# board.net
KiCad netlist of a schematic drawn in EAGLE
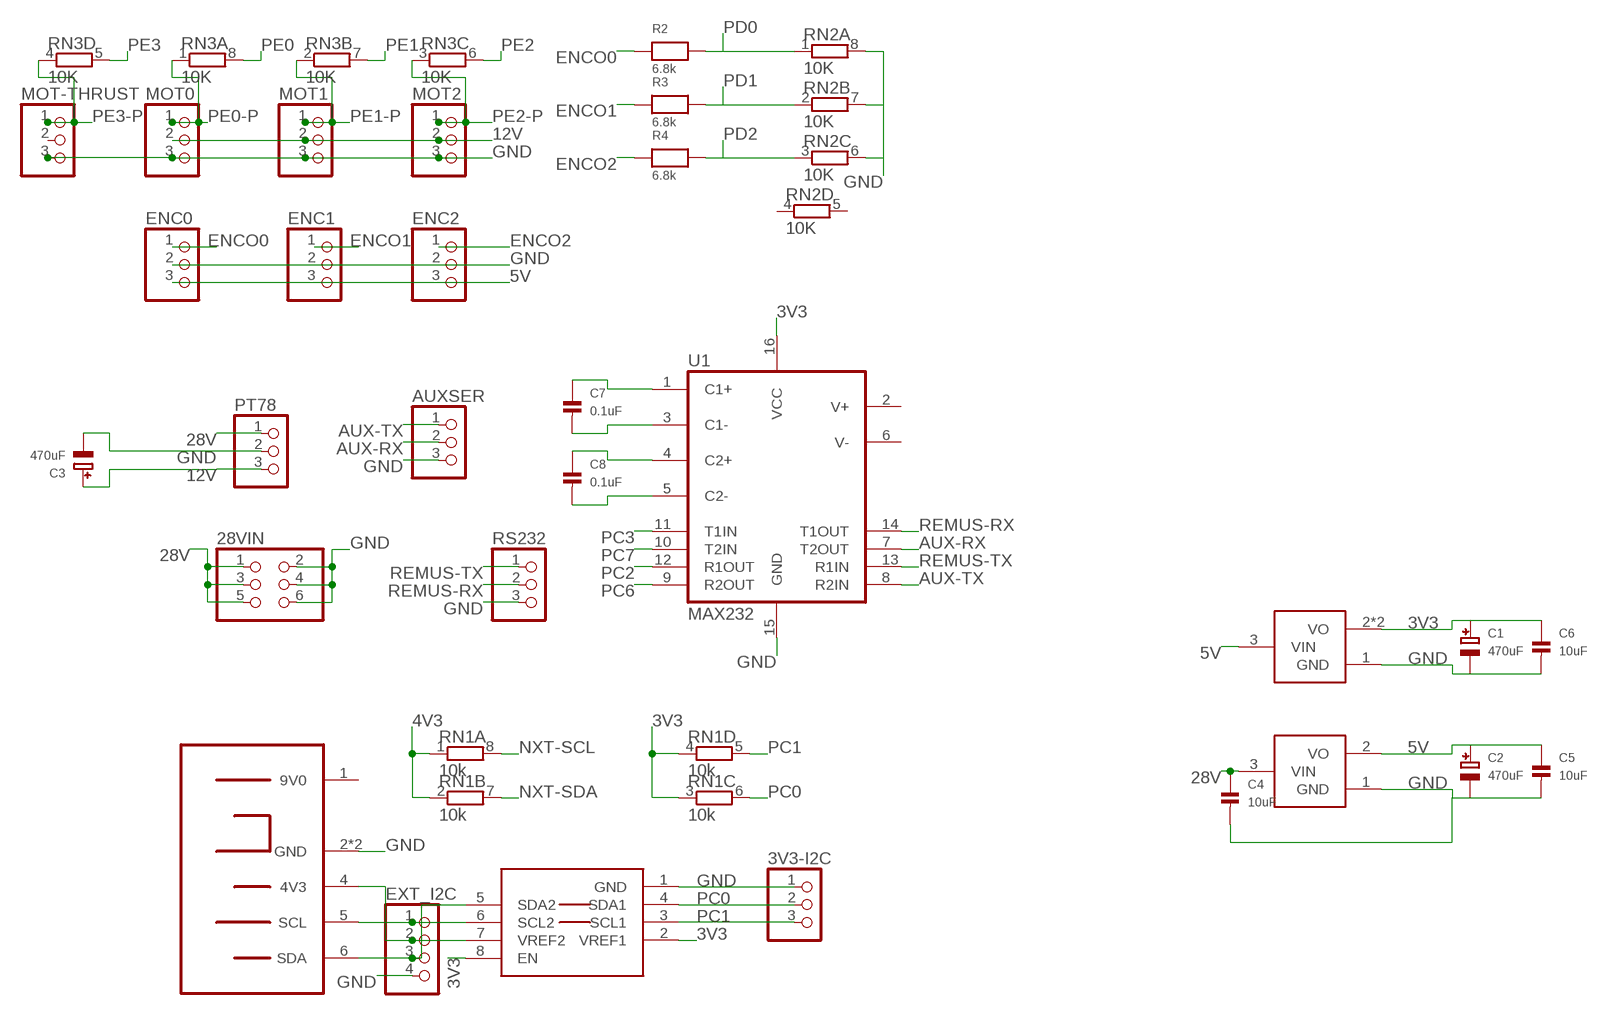
[diagram p0: schematic, sheet 1]
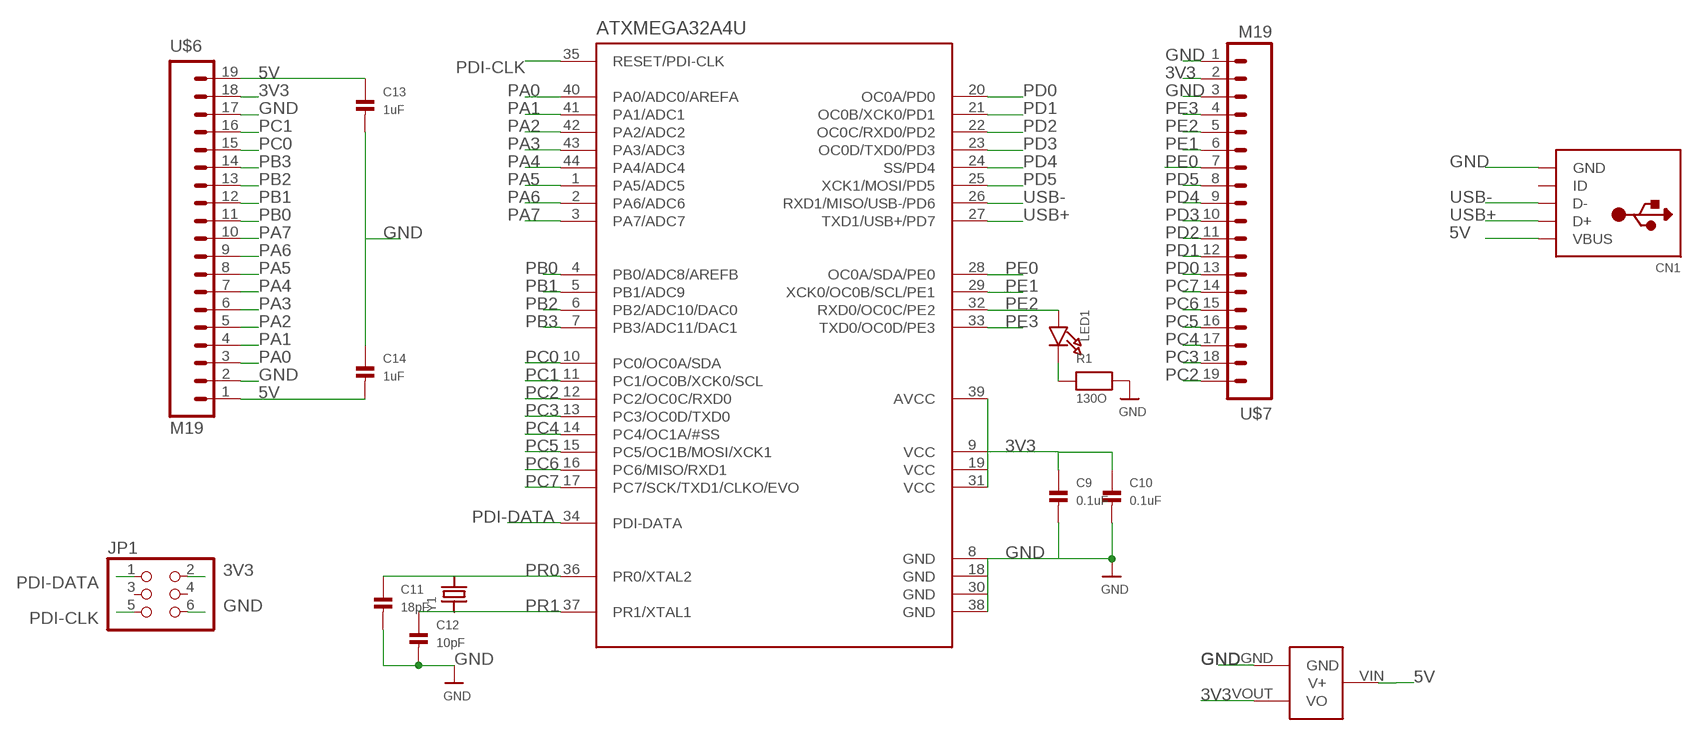
[diagram p1: schematic, sheet 2]

(export (version "E")
  (design (tool "Eeschema 10.0.6"))
  (components
    (comp (ref "ATXMEGA32A4U")
      (value "ATXMEGAXXA4U-AU")
      (footprint "eagle-import:TQFP-44")
      (libsource (lib "eagle-import") (part "ATXMEGAXXA4U-AU"))
    )
    (comp (ref "C9")
      (value "0.1uF")
      (footprint "eagle-import:0603")
      (libsource (lib "eagle-import") (part "CAP_CERAMIC0603"))
    )
    (comp (ref "C10")
      (value "0.1uF")
      (footprint "eagle-import:0603")
      (libsource (lib "eagle-import") (part "CAP_CERAMIC0603"))
    )
    (comp (ref "C11")
      (value "18pF")
      (footprint "eagle-import:0603")
      (libsource (lib "eagle-import") (part "CAP_CERAMIC0603"))
    )
    (comp (ref "C12")
      (value "10pF")
      (footprint "eagle-import:0603")
      (libsource (lib "eagle-import") (part "CAP_CERAMIC0603"))
    )
    (comp (ref "C13")
      (value "1uF")
      (footprint "eagle-import:0603")
      (libsource (lib "eagle-import") (part "CAP_CERAMIC0603"))
    )
    (comp (ref "C14")
      (value "1uF")
      (footprint "eagle-import:0603")
      (libsource (lib "eagle-import") (part "CAP_CERAMIC0603"))
    )
    (comp (ref "CN1")
      (value "USBMICROB")
      (footprint "eagle-import:USB-MICROB")
      (libsource (lib "eagle-import") (part "USBMICROB"))
    )
    (comp (ref "JP1")
      (value "HEADER-2X3")
      (footprint "eagle-import:2X03")
      (libsource (lib "eagle-import") (part "HEADER-2X3"))
    )
    (comp (ref "LED1")
      (value "LED0603")
      (footprint "eagle-import:CHIPLED_0603")
      (libsource (lib "eagle-import") (part "LED0603"))
    )
    (comp (ref "R1")
      (value "130O")
      (footprint "eagle-import:0603")
      (libsource (lib "eagle-import") (part "RESISTOR0603"))
    )
    (comp (ref "U$5")
      (value "MCP1700")
      (footprint "eagle-import:SOT23-3")
      (libsource (lib "eagle-import") (part "MCP1700"))
    )
    (comp (ref "U$6")
      (value "M19")
      (footprint "eagle-import:1X19")
      (libsource (lib "eagle-import") (part "M19"))
    )
    (comp (ref "U$7")
      (value "M19")
      (footprint "eagle-import:1X19")
      (libsource (lib "eagle-import") (part "M19"))
    )
    (comp (ref "Y1")
      (value "CRYSTAL")
      (footprint "eagle-import:NX8045GB")
      (libsource (lib "eagle-import") (part "CRYSTAL"))
    )
    (comp (ref "3V3-I2C")
      (value "HEADER-1X3ROUND")
      (footprint "eagle-import:1X03_ROUND")
      (libsource (lib "eagle-import") (part "HEADER-1X3ROUND"))
    )
    (comp (ref "28VIN")
      (value "HEADER-2X3")
      (footprint "eagle-import:2X03")
      (libsource (lib "eagle-import") (part "HEADER-2X3"))
    )
    (comp (ref "AUXSER")
      (value "HEADER-1X3ROUND")
      (footprint "eagle-import:1X03_ROUND")
      (libsource (lib "eagle-import") (part "HEADER-1X3ROUND"))
    )
    (comp (ref "C1")
      (value "470uF")
      (footprint "eagle-import:EIA7343-31_D-W")
      (libsource (lib "eagle-import") (part "CAP_TANTALUMD/7343_WAVE"))
    )
    (comp (ref "C2")
      (value "470uF")
      (footprint "eagle-import:EIA7343-31_D-W")
      (libsource (lib "eagle-import") (part "CAP_TANTALUMD/7343_WAVE"))
    )
    (comp (ref "C3")
      (value "470uF")
      (footprint "eagle-import:EIA7343-31_D-W")
      (libsource (lib "eagle-import") (part "CAP_TANTALUMD/7343_WAVE"))
    )
    (comp (ref "C4")
      (value "10uF")
      (footprint "eagle-import:1206")
      (libsource (lib "eagle-import") (part "CAP_CERAMIC1206"))
    )
    (comp (ref "C5")
      (value "10uF")
      (footprint "eagle-import:1206")
      (libsource (lib "eagle-import") (part "CAP_CERAMIC1206"))
    )
    (comp (ref "C6")
      (value "10uF")
      (footprint "eagle-import:1206")
      (libsource (lib "eagle-import") (part "CAP_CERAMIC1206"))
    )
    (comp (ref "C7")
      (value "0.1uF")
      (footprint "eagle-import:0603")
      (libsource (lib "eagle-import") (part "CAP_CERAMIC0603"))
    )
    (comp (ref "C8")
      (value "0.1uF")
      (footprint "eagle-import:0603")
      (libsource (lib "eagle-import") (part "CAP_CERAMIC0603"))
    )
    (comp (ref "ENC0")
      (value "HEADER-1X3ROUND")
      (footprint "eagle-import:1X03_ROUND")
      (libsource (lib "eagle-import") (part "HEADER-1X3ROUND"))
    )
    (comp (ref "ENC1")
      (value "HEADER-1X3ROUND")
      (footprint "eagle-import:1X03_ROUND")
      (libsource (lib "eagle-import") (part "HEADER-1X3ROUND"))
    )
    (comp (ref "ENC2")
      (value "HEADER-1X3ROUND")
      (footprint "eagle-import:1X03_ROUND")
      (libsource (lib "eagle-import") (part "HEADER-1X3ROUND"))
    )
    (comp (ref "EXT_I2C")
      (value "HEADER-1X4ROUND")
      (footprint "eagle-import:1X04_ROUND")
      (libsource (lib "eagle-import") (part "HEADER-1X4ROUND"))
    )
    (comp (ref "MOT-THRUST")
      (value "HEADER-1X3ROUND")
      (footprint "eagle-import:1X03_ROUND")
      (libsource (lib "eagle-import") (part "HEADER-1X3ROUND"))
    )
    (comp (ref "MOT0")
      (value "HEADER-1X3ROUND")
      (footprint "eagle-import:1X03_ROUND")
      (libsource (lib "eagle-import") (part "HEADER-1X3ROUND"))
    )
    (comp (ref "MOT1")
      (value "HEADER-1X3ROUND")
      (footprint "eagle-import:1X03_ROUND")
      (libsource (lib "eagle-import") (part "HEADER-1X3ROUND"))
    )
    (comp (ref "MOT2")
      (value "HEADER-1X3ROUND")
      (footprint "eagle-import:1X03_ROUND")
      (libsource (lib "eagle-import") (part "HEADER-1X3ROUND"))
    )
    (comp (ref "PT78")
      (value "HEADER-1X3ROUND")
      (footprint "eagle-import:1X03_ROUND")
      (libsource (lib "eagle-import") (part "HEADER-1X3ROUND"))
    )
    (comp (ref "R2")
      (value "6.8k")
      (footprint "eagle-import:0603")
      (libsource (lib "eagle-import") (part "RESISTOR0603"))
    )
    (comp (ref "R3")
      (value "6.8k")
      (footprint "eagle-import:0603")
      (libsource (lib "eagle-import") (part "RESISTOR0603"))
    )
    (comp (ref "R4")
      (value "6.8k")
      (footprint "eagle-import:0603")
      (libsource (lib "eagle-import") (part "RESISTOR0603"))
    )
    (comp (ref "RN1")
      (value "10k")
      (footprint "eagle-import:RN8P-4R-CRA06S")
      (libsource (lib "eagle-import") (part "RNETWORK"))
    )
    (comp (ref "RN2")
      (value "10K")
      (footprint "eagle-import:RN8P-4R-CRA06S")
      (libsource (lib "eagle-import") (part "RNETWORK"))
    )
    (comp (ref "RN3")
      (value "10K")
      (footprint "eagle-import:RN8P-4R-CRA06S")
      (libsource (lib "eagle-import") (part "RNETWORK"))
    )
    (comp (ref "RS232")
      (value "HEADER-1X3ROUND")
      (footprint "eagle-import:1X03_ROUND")
      (libsource (lib "eagle-import") (part "HEADER-1X3ROUND"))
    )
    (comp (ref "U$1")
      (value "PCA9306")
      (footprint "eagle-import:SO-08")
      (libsource (lib "eagle-import") (part "PCA9306"))
    )
    (comp (ref "U$2")
      (value "NXT-CONNECTOR")
      (footprint "eagle-import:NXT-FOOTPRINT")
      (libsource (lib "eagle-import") (part "NXT-CONNECTOR"))
    )
    (comp (ref "U$3")
      (value "VREGAP1117")
      (footprint "eagle-import:SOT223")
      (libsource (lib "eagle-import") (part "VREGAP1117"))
    )
    (comp (ref "U$4")
      (value "VREGIFX27001")
      (footprint "eagle-import:TO252")
      (libsource (lib "eagle-import") (part "VREGIFX27001"))
    )
    (comp (ref "U1")
      (value "MAX232")
      (footprint "eagle-import:SO-16")
      (libsource (lib "eagle-import") (part "MAX232"))
    )
  )
  (nets
    (net (code "1") (name "3V3") (class "Default")
      (node (ref "ATXMEGA32A4U") (pin "19") (pinfunction "VCC_19") (pintype "power_in"))
      (node (ref "ATXMEGA32A4U") (pin "31") (pinfunction "VCC_31") (pintype "power_in"))
      (node (ref "ATXMEGA32A4U") (pin "39") (pinfunction "AVCC_39") (pintype "power_in"))
      (node (ref "ATXMEGA32A4U") (pin "9") (pinfunction "VCC_9") (pintype "power_in"))
      (node (ref "C1") (pin "+") (pinfunction "+_+") (pintype "passive"))
      (node (ref "C10") (pin "1") (pinfunction "P$1_1") (pintype "passive"))
      (node (ref "C6") (pin "1") (pinfunction "P$1_1") (pintype "passive"))
      (node (ref "C9") (pin "1") (pinfunction "P$1_1") (pintype "passive"))
      (node (ref "JP1") (pin "2") (pinfunction "2_2") (pintype "passive"))
      (node (ref "RN1") (pin "3") (pinfunction "1_3") (pintype "passive"))
      (node (ref "RN1") (pin "4") (pinfunction "1_4") (pintype "passive"))
      (node (ref "U$1") (pin "2") (pinfunction "VREF1_2") (pintype "bidirectional"))
      (node (ref "U$1") (pin "8") (pinfunction "EN_8") (pintype "bidirectional"))
      (node (ref "U$3") (pin "2") (pinfunction "VO_2") (pintype "bidirectional"))
      (node (ref "U$3") (pin "4") (pinfunction "VO_4") (pintype "bidirectional"))
      (node (ref "U$5") (pin "VOUT") (pinfunction "VO_VOUT") (pintype "bidirectional"))
      (node (ref "U$6") (pin "18") (pinfunction "18_18") (pintype "passive"))
      (node (ref "U$7") (pin "2") (pinfunction "2_2") (pintype "passive"))
      (node (ref "U1") (pin "16") (pinfunction "VCC_16") (pintype "bidirectional"))
    )
    (net (code "2") (name "4V3") (class "Default")
      (node (ref "EXT_I2C") (pin "2") (pinfunction "2_2") (pintype "passive"))
      (node (ref "RN1") (pin "1") (pinfunction "1_1") (pintype "passive"))
      (node (ref "RN1") (pin "2") (pinfunction "1_2") (pintype "passive"))
      (node (ref "U$1") (pin "7") (pinfunction "VREF2_7") (pintype "bidirectional"))
      (node (ref "U$2") (pin "4") (pinfunction "4V3_4") (pintype "bidirectional"))
    )
    (net (code "3") (name "5V") (class "Default")
      (node (ref "C13") (pin "1") (pinfunction "P$1_1") (pintype "passive"))
      (node (ref "C14") (pin "2") (pinfunction "P$2_2") (pintype "passive"))
      (node (ref "C2") (pin "+") (pinfunction "+_+") (pintype "passive"))
      (node (ref "C5") (pin "1") (pinfunction "P$1_1") (pintype "passive"))
      (node (ref "CN1") (pin "P1") (pinfunction "VBUS_P1") (pintype "power_in"))
      (node (ref "ENC0") (pin "3") (pinfunction "3_3") (pintype "passive"))
      (node (ref "ENC1") (pin "3") (pinfunction "3_3") (pintype "passive"))
      (node (ref "ENC2") (pin "3") (pinfunction "3_3") (pintype "passive"))
      (node (ref "U$3") (pin "3") (pinfunction "VIN_3") (pintype "bidirectional"))
      (node (ref "U$4") (pin "2") (pinfunction "VO_2") (pintype "bidirectional"))
      (node (ref "U$5") (pin "VIN") (pinfunction "V+_VIN") (pintype "bidirectional"))
      (node (ref "U$6") (pin "1") (pinfunction "1_1") (pintype "passive"))
      (node (ref "U$6") (pin "19") (pinfunction "19_19") (pintype "passive"))
    )
    (net (code "4") (name "12V") (class "Default")
      (node (ref "C3") (pin "+") (pinfunction "+_+") (pintype "passive"))
      (node (ref "MOT0") (pin "2") (pinfunction "2_2") (pintype "passive"))
      (node (ref "MOT1") (pin "2") (pinfunction "2_2") (pintype "passive"))
      (node (ref "MOT2") (pin "2") (pinfunction "2_2") (pintype "passive"))
      (node (ref "PT78") (pin "3") (pinfunction "3_3") (pintype "passive"))
    )
    (net (code "5") (name "28V") (class "Default")
      (node (ref "28VIN") (pin "1") (pinfunction "1_1") (pintype "passive"))
      (node (ref "28VIN") (pin "3") (pinfunction "3_3") (pintype "passive"))
      (node (ref "28VIN") (pin "5") (pinfunction "5_5") (pintype "passive"))
      (node (ref "C4") (pin "1") (pinfunction "P$1_1") (pintype "passive"))
      (node (ref "PT78") (pin "1") (pinfunction "1_1") (pintype "passive"))
      (node (ref "U$4") (pin "3") (pinfunction "VIN_3") (pintype "bidirectional"))
    )
    (net (code "6") (name "AUX-RX") (class "Default")
      (node (ref "AUXSER") (pin "2") (pinfunction "2_2") (pintype "passive"))
      (node (ref "U1") (pin "7") (pinfunction "T2OUT_7") (pintype "output"))
    )
    (net (code "7") (name "AUX-TX") (class "Default")
      (node (ref "AUXSER") (pin "1") (pinfunction "1_1") (pintype "passive"))
      (node (ref "U1") (pin "8") (pinfunction "R2IN_8") (pintype "input"))
    )
    (net (code "8") (name "ENCO0") (class "Default")
      (node (ref "ENC0") (pin "1") (pinfunction "1_1") (pintype "passive"))
      (node (ref "R2") (pin "1") (pinfunction "1_1") (pintype "passive"))
    )
    (net (code "9") (name "ENCO1") (class "Default")
      (node (ref "ENC1") (pin "1") (pinfunction "1_1") (pintype "passive"))
      (node (ref "R3") (pin "1") (pinfunction "1_1") (pintype "passive"))
    )
    (net (code "10") (name "ENCO2") (class "Default")
      (node (ref "ENC2") (pin "1") (pinfunction "1_1") (pintype "passive"))
      (node (ref "R4") (pin "1") (pinfunction "1_1") (pintype "passive"))
    )
    (net (code "11") (name "GND") (class "Default")
      (node (ref "28VIN") (pin "2") (pinfunction "2_2") (pintype "passive"))
      (node (ref "28VIN") (pin "4") (pinfunction "4_4") (pintype "passive"))
      (node (ref "28VIN") (pin "6") (pinfunction "6_6") (pintype "passive"))
      (node (ref "3V3-I2C") (pin "1") (pinfunction "1_1") (pintype "passive"))
      (node (ref "ATXMEGA32A4U") (pin "18") (pinfunction "GND_18") (pintype "power_in"))
      (node (ref "ATXMEGA32A4U") (pin "30") (pinfunction "GND_30") (pintype "power_in"))
      (node (ref "ATXMEGA32A4U") (pin "38") (pinfunction "GND_38") (pintype "power_in"))
      (node (ref "ATXMEGA32A4U") (pin "8") (pinfunction "GND_8") (pintype "power_in"))
      (node (ref "AUXSER") (pin "3") (pinfunction "3_3") (pintype "passive"))
      (node (ref "C1") (pin "-") (pinfunction "-_-") (pintype "passive"))
      (node (ref "C10") (pin "2") (pinfunction "P$2_2") (pintype "passive"))
      (node (ref "C11") (pin "2") (pinfunction "P$2_2") (pintype "passive"))
      (node (ref "C12") (pin "2") (pinfunction "P$2_2") (pintype "passive"))
      (node (ref "C13") (pin "2") (pinfunction "P$2_2") (pintype "passive"))
      (node (ref "C14") (pin "1") (pinfunction "P$1_1") (pintype "passive"))
      (node (ref "C3") (pin "-") (pinfunction "-_-") (pintype "passive"))
      (node (ref "C4") (pin "2") (pinfunction "P$2_2") (pintype "passive"))
      (node (ref "C5") (pin "2") (pinfunction "P$2_2") (pintype "passive"))
      (node (ref "C6") (pin "2") (pinfunction "P$2_2") (pintype "passive"))
      (node (ref "C9") (pin "2") (pinfunction "P$2_2") (pintype "passive"))
      (node (ref "CN1") (pin "P5") (pinfunction "GND_P5") (pintype "power_in"))
      (node (ref "ENC0") (pin "2") (pinfunction "2_2") (pintype "passive"))
      (node (ref "ENC1") (pin "2") (pinfunction "2_2") (pintype "passive"))
      (node (ref "ENC2") (pin "2") (pinfunction "2_2") (pintype "passive"))
      (node (ref "EXT_I2C") (pin "4") (pinfunction "4_4") (pintype "passive"))
      (node (ref "JP1") (pin "6") (pinfunction "6_6") (pintype "passive"))
      (node (ref "MOT-THRUST") (pin "3") (pinfunction "3_3") (pintype "passive"))
      (node (ref "MOT0") (pin "3") (pinfunction "3_3") (pintype "passive"))
      (node (ref "MOT1") (pin "3") (pinfunction "3_3") (pintype "passive"))
      (node (ref "MOT2") (pin "3") (pinfunction "3_3") (pintype "passive"))
      (node (ref "PT78") (pin "2") (pinfunction "2_2") (pintype "passive"))
      (node (ref "R1") (pin "2") (pinfunction "2_2") (pintype "passive"))
      (node (ref "RN2") (pin "6") (pinfunction "2_6") (pintype "passive"))
      (node (ref "RN2") (pin "7") (pinfunction "2_7") (pintype "passive"))
      (node (ref "RN2") (pin "8") (pinfunction "2_8") (pintype "passive"))
      (node (ref "RS232") (pin "3") (pinfunction "3_3") (pintype "passive"))
      (node (ref "U$1") (pin "1") (pinfunction "GND_1") (pintype "bidirectional"))
      (node (ref "U$2") (pin "2") (pinfunction "GND_2") (pintype "bidirectional"))
      (node (ref "U$2") (pin "3") (pinfunction "GND_3") (pintype "bidirectional"))
      (node (ref "U$3") (pin "1") (pinfunction "GND_1") (pintype "bidirectional"))
      (node (ref "U$4") (pin "1") (pinfunction "GND_1") (pintype "bidirectional"))
      (node (ref "U$5") (pin "GND") (pinfunction "GND_GND") (pintype "bidirectional"))
      (node (ref "U$6") (pin "17") (pinfunction "17_17") (pintype "passive"))
      (node (ref "U$6") (pin "2") (pinfunction "2_2") (pintype "passive"))
      (node (ref "U$7") (pin "1") (pinfunction "1_1") (pintype "passive"))
      (node (ref "U$7") (pin "3") (pinfunction "3_3") (pintype "passive"))
      (node (ref "U1") (pin "15") (pinfunction "GND_15") (pintype "bidirectional"))
    )
    (net (code "12") (name "NXT-SCL") (class "Default")
      (node (ref "EXT_I2C") (pin "1") (pinfunction "1_1") (pintype "passive"))
      (node (ref "RN1") (pin "8") (pinfunction "2_8") (pintype "passive"))
      (node (ref "U$1") (pin "6") (pinfunction "SCL2_6") (pintype "bidirectional"))
      (node (ref "U$2") (pin "5") (pinfunction "SCL_5") (pintype "bidirectional"))
    )
    (net (code "13") (name "NXT-SDA") (class "Default")
      (node (ref "EXT_I2C") (pin "3") (pinfunction "3_3") (pintype "passive"))
      (node (ref "RN1") (pin "7") (pinfunction "2_7") (pintype "passive"))
      (node (ref "U$1") (pin "5") (pinfunction "SDA2_5") (pintype "bidirectional"))
      (node (ref "U$2") (pin "6") (pinfunction "SDA_6") (pintype "bidirectional"))
    )
    (net (code "14") (name "Net-(C7-P$1)") (class "Default")
      (node (ref "C7") (pin "1") (pinfunction "P$1_1") (pintype "passive"))
      (node (ref "U1") (pin "1") (pinfunction "C1+_1") (pintype "bidirectional"))
    )
    (net (code "15") (name "Net-(C7-P$2)") (class "Default")
      (node (ref "C7") (pin "2") (pinfunction "P$2_2") (pintype "passive"))
      (node (ref "U1") (pin "3") (pinfunction "C1-_3") (pintype "bidirectional"))
    )
    (net (code "16") (name "Net-(C8-P$1)") (class "Default")
      (node (ref "C8") (pin "1") (pinfunction "P$1_1") (pintype "passive"))
      (node (ref "U1") (pin "4") (pinfunction "C2+_4") (pintype "bidirectional"))
    )
    (net (code "17") (name "Net-(C8-P$2)") (class "Default")
      (node (ref "C8") (pin "2") (pinfunction "P$2_2") (pintype "passive"))
      (node (ref "U1") (pin "5") (pinfunction "C2-_5") (pintype "bidirectional"))
    )
    (net (code "18") (name "Net-(LED1-PadC)") (class "Default")
      (node (ref "LED1") (pin "C") (pinfunction "C_C") (pintype "passive"))
      (node (ref "R1") (pin "1") (pinfunction "1_1") (pintype "passive"))
    )
    (net (code "19") (name "PA0") (class "Default")
      (node (ref "ATXMEGA32A4U") (pin "40") (pinfunction "PA0/ADC0/AREFA_40") (pintype "bidirectional"))
      (node (ref "U$6") (pin "3") (pinfunction "3_3") (pintype "passive"))
    )
    (net (code "20") (name "PA1") (class "Default")
      (node (ref "ATXMEGA32A4U") (pin "41") (pinfunction "PA1/ADC1_41") (pintype "bidirectional"))
      (node (ref "U$6") (pin "4") (pinfunction "4_4") (pintype "passive"))
    )
    (net (code "21") (name "PA2") (class "Default")
      (node (ref "ATXMEGA32A4U") (pin "42") (pinfunction "PA2/ADC2_42") (pintype "bidirectional"))
      (node (ref "U$6") (pin "5") (pinfunction "5_5") (pintype "passive"))
    )
    (net (code "22") (name "PA3") (class "Default")
      (node (ref "ATXMEGA32A4U") (pin "43") (pinfunction "PA3/ADC3_43") (pintype "bidirectional"))
      (node (ref "U$6") (pin "6") (pinfunction "6_6") (pintype "passive"))
    )
    (net (code "23") (name "PA4") (class "Default")
      (node (ref "ATXMEGA32A4U") (pin "44") (pinfunction "PA4/ADC4_44") (pintype "bidirectional"))
      (node (ref "U$6") (pin "7") (pinfunction "7_7") (pintype "passive"))
    )
    (net (code "24") (name "PA5") (class "Default")
      (node (ref "ATXMEGA32A4U") (pin "1") (pinfunction "PA5/ADC5_1") (pintype "bidirectional"))
      (node (ref "U$6") (pin "8") (pinfunction "8_8") (pintype "passive"))
    )
    (net (code "25") (name "PA6") (class "Default")
      (node (ref "ATXMEGA32A4U") (pin "2") (pinfunction "PA6/ADC6_2") (pintype "bidirectional"))
      (node (ref "U$6") (pin "9") (pinfunction "9_9") (pintype "passive"))
    )
    (net (code "26") (name "PA7") (class "Default")
      (node (ref "ATXMEGA32A4U") (pin "3") (pinfunction "PA7/ADC7_3") (pintype "bidirectional"))
      (node (ref "U$6") (pin "10") (pinfunction "10_10") (pintype "passive"))
    )
    (net (code "27") (name "PB0") (class "Default")
      (node (ref "ATXMEGA32A4U") (pin "4") (pinfunction "PB0/ADC8/AREFB_4") (pintype "bidirectional"))
      (node (ref "U$6") (pin "11") (pinfunction "11_11") (pintype "passive"))
    )
    (net (code "28") (name "PB1") (class "Default")
      (node (ref "ATXMEGA32A4U") (pin "5") (pinfunction "PB1/ADC9_5") (pintype "bidirectional"))
      (node (ref "U$6") (pin "12") (pinfunction "12_12") (pintype "passive"))
    )
    (net (code "29") (name "PB2") (class "Default")
      (node (ref "ATXMEGA32A4U") (pin "6") (pinfunction "PB2/ADC10/DAC0_6") (pintype "bidirectional"))
      (node (ref "U$6") (pin "13") (pinfunction "13_13") (pintype "passive"))
    )
    (net (code "30") (name "PB3") (class "Default")
      (node (ref "ATXMEGA32A4U") (pin "7") (pinfunction "PB3/ADC11/DAC1_7") (pintype "bidirectional"))
      (node (ref "U$6") (pin "14") (pinfunction "14_14") (pintype "passive"))
    )
    (net (code "31") (name "PC0") (class "Default")
      (node (ref "3V3-I2C") (pin "2") (pinfunction "2_2") (pintype "passive"))
      (node (ref "ATXMEGA32A4U") (pin "10") (pinfunction "PC0/OC0A/SDA_10") (pintype "bidirectional"))
      (node (ref "RN1") (pin "6") (pinfunction "2_6") (pintype "passive"))
      (node (ref "U$1") (pin "4") (pinfunction "SDA1_4") (pintype "bidirectional"))
      (node (ref "U$6") (pin "15") (pinfunction "15_15") (pintype "passive"))
    )
    (net (code "32") (name "PC1") (class "Default")
      (node (ref "3V3-I2C") (pin "3") (pinfunction "3_3") (pintype "passive"))
      (node (ref "ATXMEGA32A4U") (pin "11") (pinfunction "PC1/OC0B/XCK0/SCL_11") (pintype "bidirectional"))
      (node (ref "RN1") (pin "5") (pinfunction "2_5") (pintype "passive"))
      (node (ref "U$1") (pin "3") (pinfunction "SCL1_3") (pintype "bidirectional"))
      (node (ref "U$6") (pin "16") (pinfunction "16_16") (pintype "passive"))
    )
    (net (code "33") (name "PC2") (class "Default")
      (node (ref "ATXMEGA32A4U") (pin "12") (pinfunction "PC2/OC0C/RXD0_12") (pintype "bidirectional"))
      (node (ref "U$7") (pin "19") (pinfunction "19_19") (pintype "passive"))
      (node (ref "U1") (pin "12") (pinfunction "R1OUT_12") (pintype "output"))
    )
    (net (code "34") (name "PC3") (class "Default")
      (node (ref "ATXMEGA32A4U") (pin "13") (pinfunction "PC3/OC0D/TXD0_13") (pintype "bidirectional"))
      (node (ref "U$7") (pin "18") (pinfunction "18_18") (pintype "passive"))
      (node (ref "U1") (pin "11") (pinfunction "T1IN_11") (pintype "input"))
    )
    (net (code "35") (name "PC4") (class "Default")
      (node (ref "ATXMEGA32A4U") (pin "14") (pinfunction "PC4/OC1A/#SS_14") (pintype "bidirectional"))
      (node (ref "U$7") (pin "17") (pinfunction "17_17") (pintype "passive"))
    )
    (net (code "36") (name "PC5") (class "Default")
      (node (ref "ATXMEGA32A4U") (pin "15") (pinfunction "PC5/OC1B/MOSI/XCK1_15") (pintype "bidirectional"))
      (node (ref "U$7") (pin "16") (pinfunction "16_16") (pintype "passive"))
    )
    (net (code "37") (name "PC6") (class "Default")
      (node (ref "ATXMEGA32A4U") (pin "16") (pinfunction "PC6/MISO/RXD1_16") (pintype "bidirectional"))
      (node (ref "U$7") (pin "15") (pinfunction "15_15") (pintype "passive"))
      (node (ref "U1") (pin "9") (pinfunction "R2OUT_9") (pintype "output"))
    )
    (net (code "38") (name "PC7") (class "Default")
      (node (ref "ATXMEGA32A4U") (pin "17") (pinfunction "PC7/SCK/TXD1/CLKO/EVO_17") (pintype "bidirectional"))
      (node (ref "U$7") (pin "14") (pinfunction "14_14") (pintype "passive"))
      (node (ref "U1") (pin "10") (pinfunction "T2IN_10") (pintype "input"))
    )
    (net (code "39") (name "PD0") (class "Default")
      (node (ref "ATXMEGA32A4U") (pin "20") (pinfunction "OC0A/PD0_20") (pintype "bidirectional"))
      (node (ref "R2") (pin "2") (pinfunction "2_2") (pintype "passive"))
      (node (ref "RN2") (pin "1") (pinfunction "1_1") (pintype "passive"))
      (node (ref "U$7") (pin "13") (pinfunction "13_13") (pintype "passive"))
    )
    (net (code "40") (name "PD1") (class "Default")
      (node (ref "ATXMEGA32A4U") (pin "21") (pinfunction "OC0B/XCK0/PD1_21") (pintype "bidirectional"))
      (node (ref "R3") (pin "2") (pinfunction "2_2") (pintype "passive"))
      (node (ref "RN2") (pin "2") (pinfunction "1_2") (pintype "passive"))
      (node (ref "U$7") (pin "12") (pinfunction "12_12") (pintype "passive"))
    )
    (net (code "41") (name "PD2") (class "Default")
      (node (ref "ATXMEGA32A4U") (pin "22") (pinfunction "OC0C/RXD0/PD2_22") (pintype "bidirectional"))
      (node (ref "R4") (pin "2") (pinfunction "2_2") (pintype "passive"))
      (node (ref "RN2") (pin "3") (pinfunction "1_3") (pintype "passive"))
      (node (ref "U$7") (pin "11") (pinfunction "11_11") (pintype "passive"))
    )
    (net (code "42") (name "PD3") (class "Default")
      (node (ref "ATXMEGA32A4U") (pin "23") (pinfunction "OC0D/TXD0/PD3_23") (pintype "bidirectional"))
      (node (ref "U$7") (pin "10") (pinfunction "10_10") (pintype "passive"))
    )
    (net (code "43") (name "PD4") (class "Default")
      (node (ref "ATXMEGA32A4U") (pin "24") (pinfunction "SS/PD4_24") (pintype "bidirectional"))
      (node (ref "U$7") (pin "9") (pinfunction "9_9") (pintype "passive"))
    )
    (net (code "44") (name "PD5") (class "Default")
      (node (ref "ATXMEGA32A4U") (pin "25") (pinfunction "XCK1/MOSI/PD5_25") (pintype "bidirectional"))
      (node (ref "U$7") (pin "8") (pinfunction "8_8") (pintype "passive"))
    )
    (net (code "45") (name "PDI-CLK") (class "Default")
      (node (ref "ATXMEGA32A4U") (pin "35") (pinfunction "RESET/PDI-CLK_35") (pintype "input"))
      (node (ref "JP1") (pin "5") (pinfunction "5_5") (pintype "passive"))
    )
    (net (code "46") (name "PDI-DATA") (class "Default")
      (node (ref "ATXMEGA32A4U") (pin "34") (pinfunction "PDI-DATA_34") (pintype "bidirectional"))
      (node (ref "JP1") (pin "1") (pinfunction "1_1") (pintype "passive"))
    )
    (net (code "47") (name "PE0") (class "Default")
      (node (ref "ATXMEGA32A4U") (pin "28") (pinfunction "OC0A/SDA/PE0_28") (pintype "bidirectional"))
      (node (ref "RN3") (pin "8") (pinfunction "2_8") (pintype "passive"))
      (node (ref "U$7") (pin "7") (pinfunction "7_7") (pintype "passive"))
    )
    (net (code "48") (name "PE0-P") (class "Default")
      (node (ref "MOT0") (pin "1") (pinfunction "1_1") (pintype "passive"))
      (node (ref "RN3") (pin "1") (pinfunction "1_1") (pintype "passive"))
    )
    (net (code "49") (name "PE1") (class "Default")
      (node (ref "ATXMEGA32A4U") (pin "29") (pinfunction "XCK0/OC0B/SCL/PE1_29") (pintype "bidirectional"))
      (node (ref "RN3") (pin "7") (pinfunction "2_7") (pintype "passive"))
      (node (ref "U$7") (pin "6") (pinfunction "6_6") (pintype "passive"))
    )
    (net (code "50") (name "PE1-P") (class "Default")
      (node (ref "MOT1") (pin "1") (pinfunction "1_1") (pintype "passive"))
      (node (ref "RN3") (pin "2") (pinfunction "1_2") (pintype "passive"))
    )
    (net (code "51") (name "PE2") (class "Default")
      (node (ref "ATXMEGA32A4U") (pin "32") (pinfunction "RXD0/OC0C/PE2_32") (pintype "bidirectional"))
      (node (ref "LED1") (pin "A") (pinfunction "A_A") (pintype "passive"))
      (node (ref "RN3") (pin "6") (pinfunction "2_6") (pintype "passive"))
      (node (ref "U$7") (pin "5") (pinfunction "5_5") (pintype "passive"))
    )
    (net (code "52") (name "PE2-P") (class "Default")
      (node (ref "MOT2") (pin "1") (pinfunction "1_1") (pintype "passive"))
      (node (ref "RN3") (pin "3") (pinfunction "1_3") (pintype "passive"))
    )
    (net (code "53") (name "PE3") (class "Default")
      (node (ref "ATXMEGA32A4U") (pin "33") (pinfunction "TXD0/OC0D/PE3_33") (pintype "bidirectional"))
      (node (ref "RN3") (pin "5") (pinfunction "2_5") (pintype "passive"))
      (node (ref "U$7") (pin "4") (pinfunction "4_4") (pintype "passive"))
    )
    (net (code "54") (name "PE3-P") (class "Default")
      (node (ref "MOT-THRUST") (pin "1") (pinfunction "1_1") (pintype "passive"))
      (node (ref "RN3") (pin "4") (pinfunction "1_4") (pintype "passive"))
    )
    (net (code "55") (name "PR0") (class "Default")
      (node (ref "ATXMEGA32A4U") (pin "36") (pinfunction "PR0/XTAL2_36") (pintype "bidirectional"))
      (node (ref "C11") (pin "1") (pinfunction "P$1_1") (pintype "passive"))
      (node (ref "Y1") (pin "P$2") (pinfunction "2_P$2") (pintype "passive"))
    )
    (net (code "56") (name "PR1") (class "Default")
      (node (ref "ATXMEGA32A4U") (pin "37") (pinfunction "PR1/XTAL1_37") (pintype "bidirectional"))
      (node (ref "C12") (pin "1") (pinfunction "P$1_1") (pintype "passive"))
      (node (ref "Y1") (pin "P$1") (pinfunction "1_P$1") (pintype "passive"))
    )
    (net (code "57") (name "REMUS-RX") (class "Default")
      (node (ref "RS232") (pin "2") (pinfunction "2_2") (pintype "passive"))
      (node (ref "U1") (pin "14") (pinfunction "T1OUT_14") (pintype "output"))
    )
    (net (code "58") (name "REMUS-TX") (class "Default")
      (node (ref "RS232") (pin "1") (pinfunction "1_1") (pintype "passive"))
      (node (ref "U1") (pin "13") (pinfunction "R1IN_13") (pintype "input"))
    )
    (net (code "59") (name "USB+") (class "Default")
      (node (ref "ATXMEGA32A4U") (pin "27") (pinfunction "TXD1/USB+/PD7_27") (pintype "bidirectional"))
      (node (ref "CN1") (pin "P3") (pinfunction "D+_P3") (pintype "bidirectional"))
    )
    (net (code "60") (name "USB-") (class "Default")
      (node (ref "ATXMEGA32A4U") (pin "26") (pinfunction "RXD1/MISO/USB-/PD6_26") (pintype "bidirectional"))
      (node (ref "CN1") (pin "P2") (pinfunction "D-_P2") (pintype "bidirectional"))
    )
    (net (code "61") (name "unconnected-(C2-Pad-)") (class "Default")
      (node (ref "C2") (pin "-") (pinfunction "-_-") (pintype "passive"))
    )
    (net (code "62") (name "unconnected-(CN1-ID-PadP4)") (class "Default")
      (node (ref "CN1") (pin "P4") (pinfunction "ID_P4") (pintype "bidirectional"))
    )
    (net (code "63") (name "unconnected-(JP1-Pad3)") (class "Default")
      (node (ref "JP1") (pin "3") (pinfunction "3_3") (pintype "passive"))
    )
    (net (code "64") (name "unconnected-(JP1-Pad4)") (class "Default")
      (node (ref "JP1") (pin "4") (pinfunction "4_4") (pintype "passive"))
    )
    (net (code "65") (name "unconnected-(MOT-THRUST-Pad2)") (class "Default")
      (node (ref "MOT-THRUST") (pin "2") (pinfunction "2_2") (pintype "passive"))
    )
    (net (code "66") (name "unconnected-(RN2D-1-Pad4)") (class "Default")
      (node (ref "RN2") (pin "4") (pinfunction "1_4") (pintype "passive"))
    )
    (net (code "67") (name "unconnected-(RN2D-2-Pad5)") (class "Default")
      (node (ref "RN2") (pin "5") (pinfunction "2_5") (pintype "passive"))
    )
    (net (code "68") (name "unconnected-(U$2-9V0-Pad1)") (class "Default")
      (node (ref "U$2") (pin "1") (pinfunction "9V0_1") (pintype "bidirectional"))
    )
    (net (code "69") (name "unconnected-(U1-V+-Pad2)") (class "Default")
      (node (ref "U1") (pin "2") (pinfunction "V+_2") (pintype "bidirectional"))
    )
    (net (code "70") (name "unconnected-(U1-V--Pad6)") (class "Default")
      (node (ref "U1") (pin "6") (pinfunction "V-_6") (pintype "bidirectional"))
    )
  )
)
